# CMM_PCB_v1_0.net
KiCad netlist of a schematic drawn in EAGLE
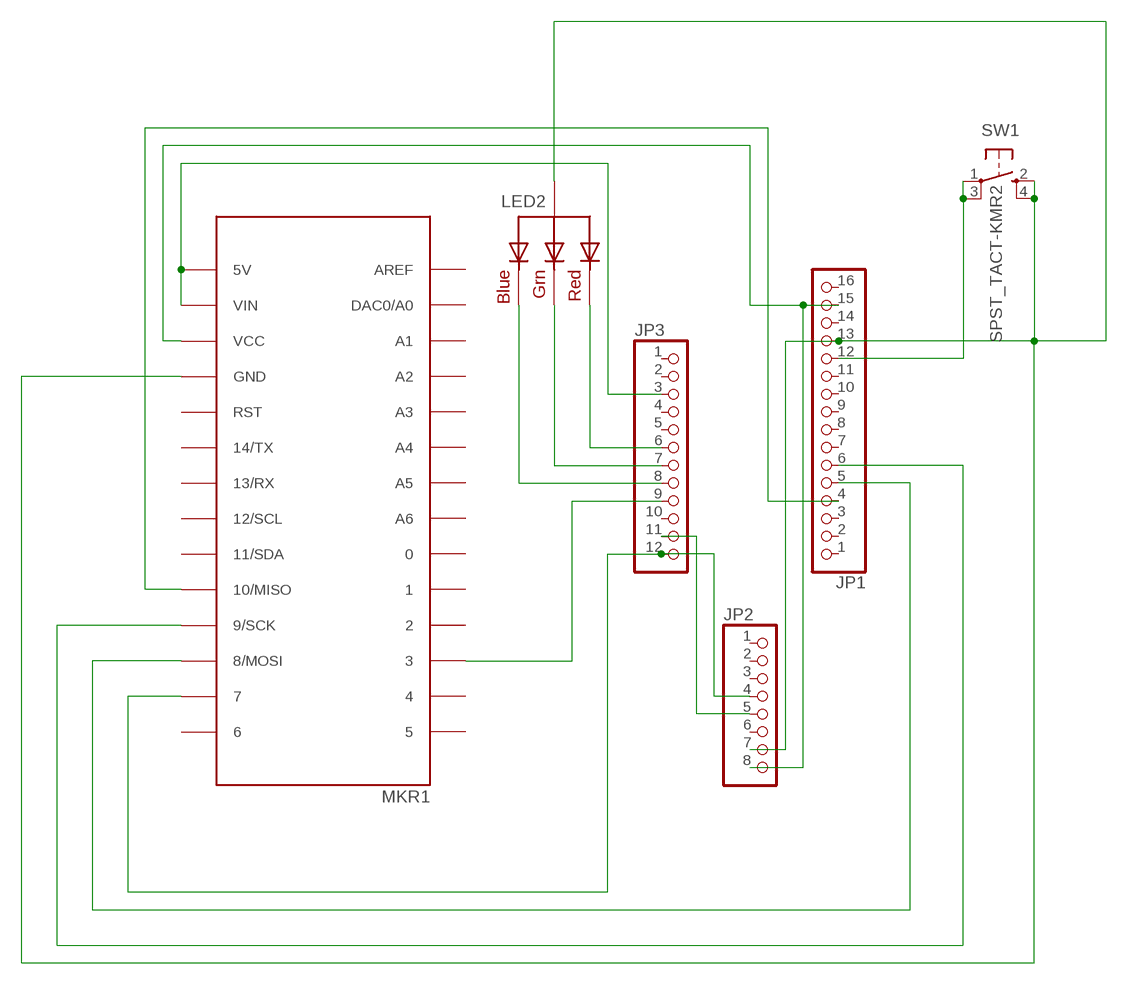
[diagram p0: schematic, sheet 1]

(export (version "E")
  (design (tool "Eeschema 10.0.6"))
  (components
    (comp (ref "JP1")
      (value "HEADER-1X16ROUND")
      (footprint "eagle-import:1X16_ROUND")
      (libsource (lib "eagle-import") (part "HEADER-1X16ROUND"))
    )
    (comp (ref "JP2")
      (value "HEADER-1X870MIL")
      (footprint "eagle-import:1X08_ROUND_70")
      (libsource (lib "eagle-import") (part "HEADER-1X870MIL"))
    )
    (comp (ref "JP3")
      (value "HEADER-1X12")
      (footprint "eagle-import:1X12_ROUND")
      (libsource (lib "eagle-import") (part "HEADER-1X12"))
    )
    (comp (ref "LED2")
      (value "RGBLED_CA-5MM")
      (footprint "eagle-import:LED5MMRGB")
      (libsource (lib "eagle-import") (part "RGBLED_CA-5MM"))
    )
    (comp (ref "MKR1")
      (value "-")
      (footprint "eagle-import:ARDUINO-UTILITY_MKRBOARD")
      (libsource (lib "eagle-import") (part "ARDUINO-UTILITY_MKRBOARDOUTLINE"))
    )
    (comp (ref "SW1")
      (value "SPST_TACT-KMR2")
      (footprint "eagle-import:KMR2")
      (libsource (lib "eagle-import") (part "SPST_TACT-KMR2"))
    )
  )
  (nets
    (net (code "1") (name "Net-(JP1-Pad15)") (class "Default")
      (node (ref "JP1") (pin "15") (pinfunction "15_15") (pintype "passive"))
      (node (ref "JP2") (pin "8") (pinfunction "8_8") (pintype "passive"))
      (node (ref "MKR1") (pin "VCC") (pinfunction "VCC_VCC") (pintype "bidirectional"))
    )
    (net (code "2") (name "Net-(JP2-Pad4)") (class "Default")
      (node (ref "JP2") (pin "4") (pinfunction "4_4") (pintype "passive"))
      (node (ref "JP3") (pin "12") (pinfunction "12_12") (pintype "passive"))
      (node (ref "MKR1") (pin "7") (pinfunction "7_7") (pintype "bidirectional"))
    )
    (net (code "3") (name "Net-(JP2-Pad5)") (class "Default")
      (node (ref "JP2") (pin "5") (pinfunction "5_5") (pintype "passive"))
      (node (ref "JP3") (pin "11") (pinfunction "11_11") (pintype "passive"))
    )
    (net (code "4") (name "Net-(JP3-Pad3)") (class "Default")
      (node (ref "JP3") (pin "3") (pinfunction "3_3") (pintype "passive"))
      (node (ref "MKR1") (pin "5V") (pinfunction "5V_5V") (pintype "bidirectional"))
      (node (ref "MKR1") (pin "VIN") (pinfunction "VIN_VIN") (pintype "bidirectional"))
    )
    (net (code "5") (name "Net-(JP3-Pad9)") (class "Default")
      (node (ref "JP3") (pin "9") (pinfunction "9_9") (pintype "passive"))
      (node (ref "MKR1") (pin "3") (pinfunction "3_3") (pintype "bidirectional"))
    )
    (net (code "6") (name "Net-(LED2-BLUE)") (class "Default")
      (node (ref "JP3") (pin "8") (pinfunction "8_8") (pintype "passive"))
      (node (ref "LED2") (pin "4") (pinfunction "BLUE_4") (pintype "bidirectional"))
    )
    (net (code "7") (name "Net-(LED2-GREEN)") (class "Default")
      (node (ref "JP3") (pin "7") (pinfunction "7_7") (pintype "passive"))
      (node (ref "LED2") (pin "3") (pinfunction "GREEN_3") (pintype "bidirectional"))
    )
    (net (code "8") (name "Net-(LED2-RED)") (class "Default")
      (node (ref "JP3") (pin "6") (pinfunction "6_6") (pintype "passive"))
      (node (ref "LED2") (pin "1") (pinfunction "RED_1") (pintype "bidirectional"))
    )
    (net (code "9") (name "Net-(LED2-VCC)") (class "Default")
      (node (ref "JP1") (pin "13") (pinfunction "13_13") (pintype "passive"))
      (node (ref "JP2") (pin "7") (pinfunction "7_7") (pintype "passive"))
      (node (ref "LED2") (pin "2") (pinfunction "VCC_2") (pintype "bidirectional"))
      (node (ref "MKR1") (pin "GND") (pinfunction "GND_GND") (pintype "bidirectional"))
      (node (ref "SW1") (pin "2") (pinfunction "S_2") (pintype "passive"))
      (node (ref "SW1") (pin "4") (pinfunction "S1_4") (pintype "passive"))
    )
    (net (code "10") (name "Net-(MKR1-8{slash}MOSI)") (class "Default")
      (node (ref "JP1") (pin "5") (pinfunction "5_5") (pintype "passive"))
      (node (ref "MKR1") (pin "8") (pinfunction "8/MOSI_8") (pintype "bidirectional"))
    )
    (net (code "11") (name "Net-(MKR1-9{slash}SCK)") (class "Default")
      (node (ref "JP1") (pin "6") (pinfunction "6_6") (pintype "passive"))
      (node (ref "MKR1") (pin "9") (pinfunction "9/SCK_9") (pintype "bidirectional"))
    )
    (net (code "12") (name "Net-(MKR1-10{slash}MISO)") (class "Default")
      (node (ref "JP1") (pin "4") (pinfunction "4_4") (pintype "passive"))
      (node (ref "MKR1") (pin "10") (pinfunction "10/MISO_10") (pintype "bidirectional"))
    )
    (net (code "13") (name "Net-(SW1-P)") (class "Default")
      (node (ref "JP1") (pin "12") (pinfunction "12_12") (pintype "passive"))
      (node (ref "SW1") (pin "1") (pinfunction "P_1") (pintype "passive"))
      (node (ref "SW1") (pin "3") (pinfunction "P1_3") (pintype "passive"))
    )
    (net (code "14") (name "unconnected-(JP1-Pad1)") (class "Default")
      (node (ref "JP1") (pin "1") (pinfunction "1_1") (pintype "passive"))
    )
    (net (code "15") (name "unconnected-(JP1-Pad2)") (class "Default")
      (node (ref "JP1") (pin "2") (pinfunction "2_2") (pintype "passive"))
    )
    (net (code "16") (name "unconnected-(JP1-Pad3)") (class "Default")
      (node (ref "JP1") (pin "3") (pinfunction "3_3") (pintype "passive"))
    )
    (net (code "17") (name "unconnected-(JP1-Pad7)") (class "Default")
      (node (ref "JP1") (pin "7") (pinfunction "7_7") (pintype "passive"))
    )
    (net (code "18") (name "unconnected-(JP1-Pad8)") (class "Default")
      (node (ref "JP1") (pin "8") (pinfunction "8_8") (pintype "passive"))
    )
    (net (code "19") (name "unconnected-(JP1-Pad9)") (class "Default")
      (node (ref "JP1") (pin "9") (pinfunction "9_9") (pintype "passive"))
    )
    (net (code "20") (name "unconnected-(JP1-Pad10)") (class "Default")
      (node (ref "JP1") (pin "10") (pinfunction "10_10") (pintype "passive"))
    )
    (net (code "21") (name "unconnected-(JP1-Pad11)") (class "Default")
      (node (ref "JP1") (pin "11") (pinfunction "11_11") (pintype "passive"))
    )
    (net (code "22") (name "unconnected-(JP1-Pad14)") (class "Default")
      (node (ref "JP1") (pin "14") (pinfunction "14_14") (pintype "passive"))
    )
    (net (code "23") (name "unconnected-(JP1-Pad16)") (class "Default")
      (node (ref "JP1") (pin "16") (pinfunction "16_16") (pintype "passive"))
    )
    (net (code "24") (name "unconnected-(JP2-Pad1)") (class "Default")
      (node (ref "JP2") (pin "1") (pinfunction "1_1") (pintype "passive"))
    )
    (net (code "25") (name "unconnected-(JP2-Pad2)") (class "Default")
      (node (ref "JP2") (pin "2") (pinfunction "2_2") (pintype "passive"))
    )
    (net (code "26") (name "unconnected-(JP2-Pad3)") (class "Default")
      (node (ref "JP2") (pin "3") (pinfunction "3_3") (pintype "passive"))
    )
    (net (code "27") (name "unconnected-(JP2-Pad6)") (class "Default")
      (node (ref "JP2") (pin "6") (pinfunction "6_6") (pintype "passive"))
    )
    (net (code "28") (name "unconnected-(JP3-Pad1)") (class "Default")
      (node (ref "JP3") (pin "1") (pinfunction "1_1") (pintype "passive"))
    )
    (net (code "29") (name "unconnected-(JP3-Pad2)") (class "Default")
      (node (ref "JP3") (pin "2") (pinfunction "2_2") (pintype "passive"))
    )
    (net (code "30") (name "unconnected-(JP3-Pad4)") (class "Default")
      (node (ref "JP3") (pin "4") (pinfunction "4_4") (pintype "passive"))
    )
    (net (code "31") (name "unconnected-(JP3-Pad5)") (class "Default")
      (node (ref "JP3") (pin "5") (pinfunction "5_5") (pintype "passive"))
    )
    (net (code "32") (name "unconnected-(JP3-Pad10)") (class "Default")
      (node (ref "JP3") (pin "10") (pinfunction "10_10") (pintype "passive"))
    )
    (net (code "33") (name "unconnected-(MKR1-11{slash}SDA-Pad11)") (class "Default")
      (node (ref "MKR1") (pin "11") (pinfunction "11/SDA_11") (pintype "bidirectional"))
    )
    (net (code "34") (name "unconnected-(MKR1-12{slash}SCL-Pad12)") (class "Default")
      (node (ref "MKR1") (pin "12") (pinfunction "12/SCL_12") (pintype "bidirectional"))
    )
    (net (code "35") (name "unconnected-(MKR1-13{slash}RX-Pad13)") (class "Default")
      (node (ref "MKR1") (pin "13") (pinfunction "13/RX_13") (pintype "bidirectional"))
    )
    (net (code "36") (name "unconnected-(MKR1-14{slash}TX-Pad14)") (class "Default")
      (node (ref "MKR1") (pin "14") (pinfunction "14/TX_14") (pintype "bidirectional"))
    )
    (net (code "37") (name "unconnected-(MKR1-DAC0{slash}A0-PadA0)") (class "Default")
      (node (ref "MKR1") (pin "A0") (pinfunction "DAC0/A0_A0") (pintype "bidirectional"))
    )
    (net (code "38") (name "unconnected-(MKR1-Pad0)") (class "Default")
      (node (ref "MKR1") (pin "0") (pinfunction "0_0") (pintype "bidirectional"))
    )
    (net (code "39") (name "unconnected-(MKR1-Pad1)") (class "Default")
      (node (ref "MKR1") (pin "1") (pinfunction "1_1") (pintype "bidirectional"))
    )
    (net (code "40") (name "unconnected-(MKR1-Pad2)") (class "Default")
      (node (ref "MKR1") (pin "2") (pinfunction "2_2") (pintype "bidirectional"))
    )
    (net (code "41") (name "unconnected-(MKR1-Pad4)") (class "Default")
      (node (ref "MKR1") (pin "4") (pinfunction "4_4") (pintype "bidirectional"))
    )
    (net (code "42") (name "unconnected-(MKR1-Pad5)") (class "Default")
      (node (ref "MKR1") (pin "5") (pinfunction "5_5") (pintype "bidirectional"))
    )
    (net (code "43") (name "unconnected-(MKR1-Pad6)") (class "Default")
      (node (ref "MKR1") (pin "6") (pinfunction "6_6") (pintype "bidirectional"))
    )
    (net (code "44") (name "unconnected-(MKR1-PadA1)") (class "Default")
      (node (ref "MKR1") (pin "A1") (pinfunction "A1_A1") (pintype "bidirectional"))
    )
    (net (code "45") (name "unconnected-(MKR1-PadA2)") (class "Default")
      (node (ref "MKR1") (pin "A2") (pinfunction "A2_A2") (pintype "bidirectional"))
    )
    (net (code "46") (name "unconnected-(MKR1-PadA3)") (class "Default")
      (node (ref "MKR1") (pin "A3") (pinfunction "A3_A3") (pintype "bidirectional"))
    )
    (net (code "47") (name "unconnected-(MKR1-PadA4)") (class "Default")
      (node (ref "MKR1") (pin "A4") (pinfunction "A4_A4") (pintype "bidirectional"))
    )
    (net (code "48") (name "unconnected-(MKR1-PadA5)") (class "Default")
      (node (ref "MKR1") (pin "A5") (pinfunction "A5_A5") (pintype "bidirectional"))
    )
    (net (code "49") (name "unconnected-(MKR1-PadA6)") (class "Default")
      (node (ref "MKR1") (pin "A6") (pinfunction "A6_A6") (pintype "bidirectional"))
    )
    (net (code "50") (name "unconnected-(MKR1-PadAREF)") (class "Default")
      (node (ref "MKR1") (pin "AREF") (pinfunction "AREF_AREF") (pintype "bidirectional"))
    )
    (net (code "51") (name "unconnected-(MKR1-PadRST)") (class "Default")
      (node (ref "MKR1") (pin "RST") (pinfunction "RST_RST") (pintype "bidirectional"))
    )
  )
)
